# LPC1768.net
KiCad netlist of a schematic drawn in Altium Designer
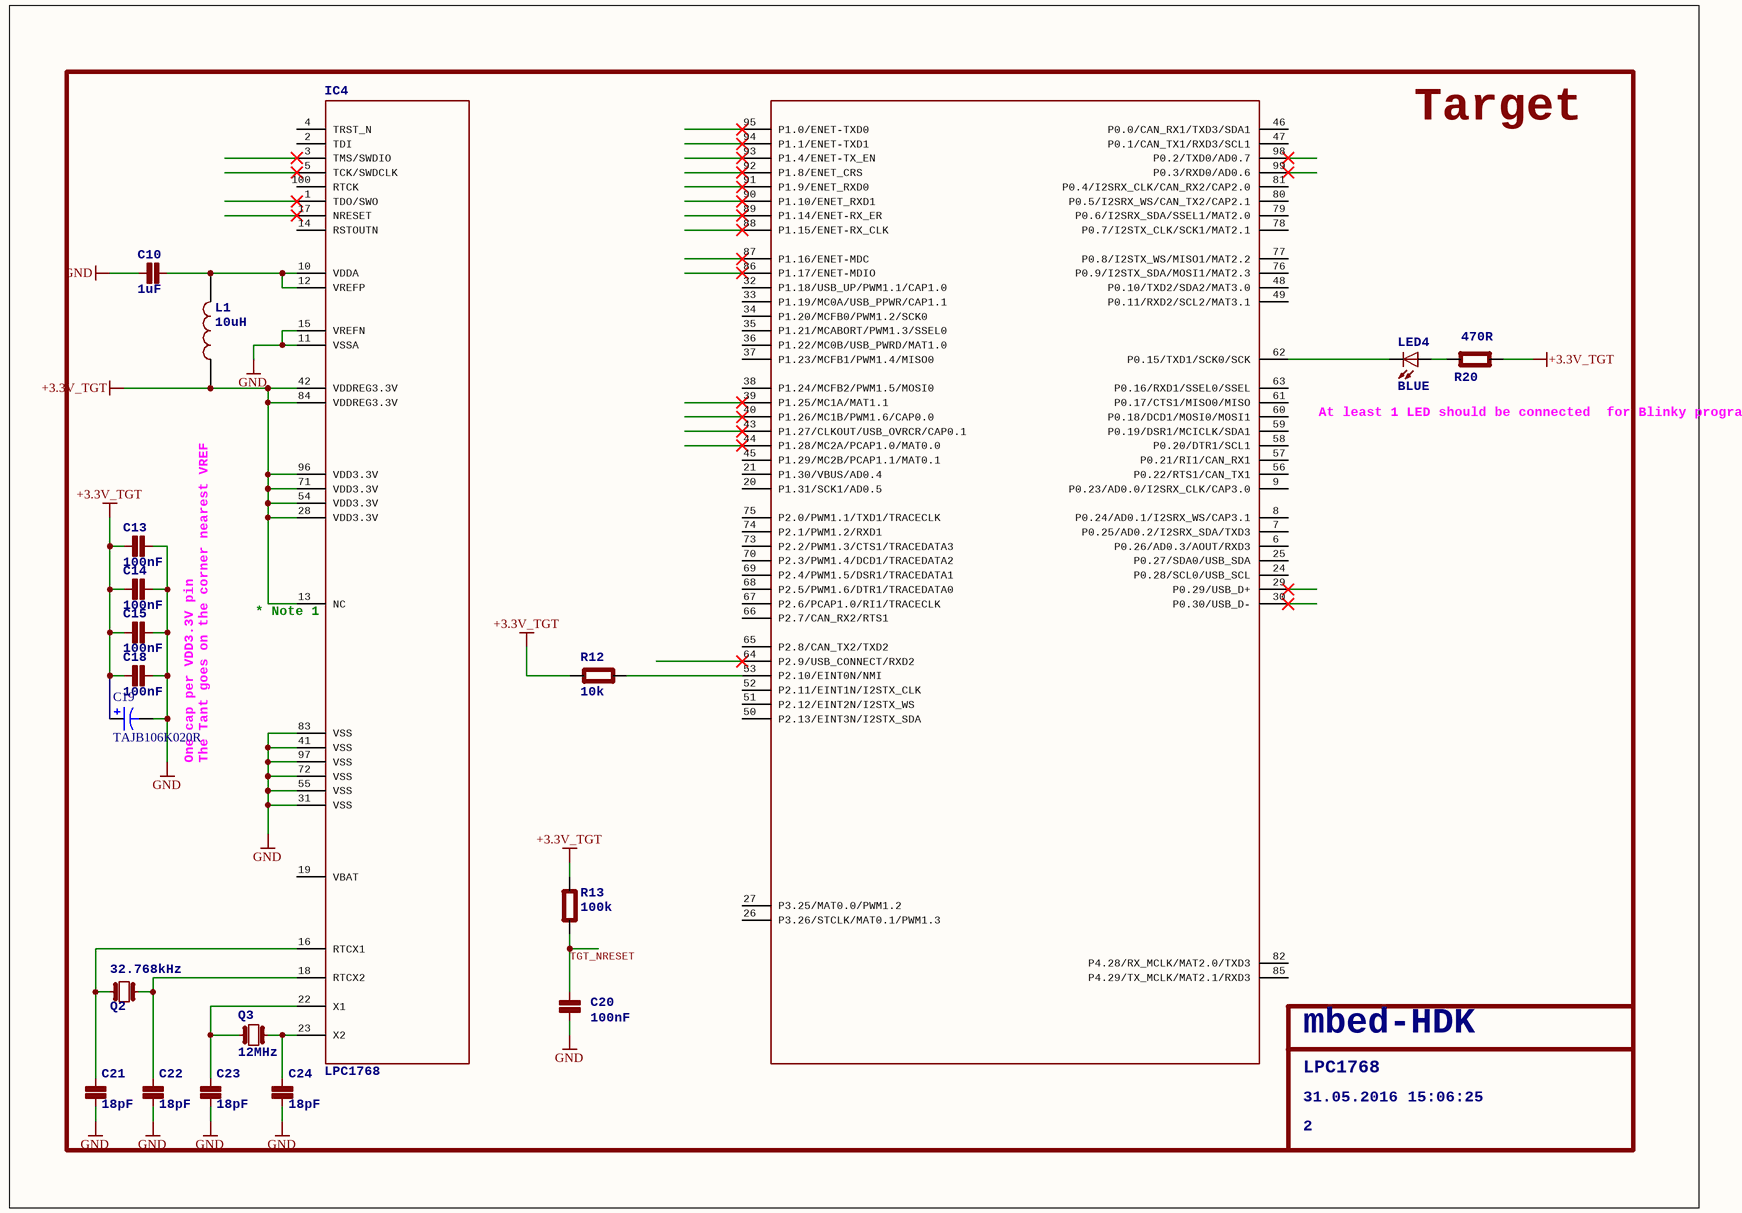
[diagram p0: LPC1768.SchDoc]

(export (version "E")
  (design (tool "Eeschema 10.0.6"))
  (components
    (comp (ref "C10") (value "1uF") (footprint "0603") (libsource (lib "") (part "C0603_2")))
    (comp (ref "C13") (value "100nF") (footprint "0603") (libsource (lib "") (part "C0603_1")))
    (comp (ref "C14") (value "100nF") (footprint "0603") (libsource (lib "") (part "C0603_1")))
    (comp (ref "C15") (value "100nF") (footprint "0603") (libsource (lib "") (part "C0603_1")))
    (comp (ref "C18") (value "100nF") (footprint "0603") (libsource (lib "") (part "C0603_1")))
    (comp (ref "C19")
      (value "TAJB106K020R")
      (footprint "AVX-CAPC3528_V")
      (description "Capacitor, Tantalum, 10uF 10% 20V MCCT-B (3528)")
      (fields (field (name "MANUFACTURER") "AVX") (field (name "TOLERANCE") "10%"))
      (libsource (lib "Altium Content Vault") (part "CMP-0279-00001-1"))
    )
    (comp (ref "C20") (value "100nF") (footprint "0603") (libsource (lib "mbed-HDK") (part "C0603")))
    (comp (ref "C21") (value "18pF") (footprint "0603") (libsource (lib "mbed-HDK") (part "C0603")))
    (comp (ref "C22") (value "18pF") (footprint "0603") (libsource (lib "mbed-HDK") (part "C0603")))
    (comp (ref "C23") (value "18pF") (footprint "0603") (libsource (lib "mbed-HDK") (part "C0603")))
    (comp (ref "C24") (value "18pF") (footprint "0603") (libsource (lib "mbed-HDK") (part "C0603")))
    (comp (ref "IC4") (value "LPC1768") (footprint "LQFP100") (libsource (lib "mbed-HDK") (part "LPC1768")))
    (comp (ref "L1") (value "10uH") (footprint "0603") (libsource (lib "mbed-HDK") (part "L")))
    (comp (ref "LED4")
      (value "BLUE")
      (footprint "CHIPLED_0603")
      (libsource (lib "mbed-HDK") (part "LED0603"))
    )
    (comp (ref "Q2") (value "32.768kHz") (footprint "FC135") (libsource (lib "mbed-HDK") (part "Q_FC135")))
    (comp (ref "Q3") (value "12MHz") (footprint "HC49UP") (libsource (lib "mbed-HDK") (part "Q_HC49UP")))
    (comp (ref "R12") (value "10k") (footprint "0603") (libsource (lib "mbed-HDK") (part "R0603")))
    (comp (ref "R13") (value "100k") (footprint "0603") (libsource (lib "mbed-HDK") (part "R0603")))
    (comp (ref "R20") (value "470R") (footprint "0603") (libsource (lib "mbed-HDK") (part "R0603")))
  )
  (nets
    (net (code "1") (name "+3.3V_TGT") (class "Default")
      (node (ref "C13") (pin "1") (pinfunction "P$1_1") (pintype "passive"))
      (node (ref "C14") (pin "1") (pinfunction "P$1_1") (pintype "passive"))
      (node (ref "C15") (pin "1") (pinfunction "P$1_1") (pintype "passive"))
      (node (ref "C18") (pin "1") (pinfunction "P$1_1") (pintype "passive"))
      (node (ref "C19") (pin "1") (pinfunction "1_1") (pintype "passive"))
      (node (ref "IC4") (pin "13") (pinfunction "NC_13") (pintype "passive"))
      (node (ref "IC4") (pin "28") (pinfunction "VDD3.3V_28") (pintype "passive"))
      (node (ref "IC4") (pin "42") (pinfunction "VDDREG3.3V_42") (pintype "passive"))
      (node (ref "IC4") (pin "54") (pinfunction "VDD3.3V_54") (pintype "passive"))
      (node (ref "IC4") (pin "71") (pinfunction "VDD3.3V_71") (pintype "passive"))
      (node (ref "IC4") (pin "84") (pinfunction "VDDREG3.3V_84") (pintype "passive"))
      (node (ref "IC4") (pin "96") (pinfunction "VDD3.3V_96") (pintype "passive"))
      (node (ref "L1") (pin "1") (pinfunction "P$1_1") (pintype "passive"))
      (node (ref "R12") (pin "1") (pinfunction "P$1_1") (pintype "passive"))
      (node (ref "R13") (pin "2") (pinfunction "P$2_2") (pintype "passive"))
      (node (ref "R20") (pin "1") (pinfunction "P$1_1") (pintype "passive"))
    )
    (net (code "2") (name "/TGT_NRESET") (class "Default")
      (node (ref "C20") (pin "2") (pinfunction "P$2_2") (pintype "passive"))
      (node (ref "R13") (pin "1") (pinfunction "P$1_1") (pintype "passive"))
    )
    (net (code "3") (name "GND") (class "Default")
      (node (ref "C10") (pin "2") (pinfunction "P$2_2") (pintype "passive"))
      (node (ref "C13") (pin "2") (pinfunction "P$2_2") (pintype "passive"))
      (node (ref "C14") (pin "2") (pinfunction "P$2_2") (pintype "passive"))
      (node (ref "C15") (pin "2") (pinfunction "P$2_2") (pintype "passive"))
      (node (ref "C18") (pin "2") (pinfunction "P$2_2") (pintype "passive"))
      (node (ref "C19") (pin "2") (pinfunction "2_2") (pintype "passive"))
      (node (ref "C20") (pin "1") (pinfunction "P$1_1") (pintype "passive"))
      (node (ref "C21") (pin "1") (pinfunction "P$1_1") (pintype "passive"))
      (node (ref "C22") (pin "1") (pinfunction "P$1_1") (pintype "passive"))
      (node (ref "C23") (pin "1") (pinfunction "P$1_1") (pintype "passive"))
      (node (ref "C24") (pin "1") (pinfunction "P$1_1") (pintype "passive"))
      (node (ref "IC4") (pin "11") (pinfunction "VSSA_11") (pintype "passive"))
      (node (ref "IC4") (pin "15") (pinfunction "VREFN_15") (pintype "passive"))
      (node (ref "IC4") (pin "31") (pinfunction "VSS_31") (pintype "passive"))
      (node (ref "IC4") (pin "41") (pinfunction "VSS_41") (pintype "passive"))
      (node (ref "IC4") (pin "55") (pinfunction "VSS_55") (pintype "passive"))
      (node (ref "IC4") (pin "72") (pinfunction "VSS_72") (pintype "passive"))
      (node (ref "IC4") (pin "83") (pinfunction "VSS_83") (pintype "passive"))
      (node (ref "IC4") (pin "97") (pinfunction "VSS_97") (pintype "passive"))
    )
    (net (code "4") (name "Net-(C10-P$1)") (class "Default")
      (node (ref "C10") (pin "1") (pinfunction "P$1_1") (pintype "passive"))
      (node (ref "IC4") (pin "10") (pinfunction "VDDA_10") (pintype "passive"))
      (node (ref "IC4") (pin "12") (pinfunction "VREFP_12") (pintype "passive"))
      (node (ref "L1") (pin "2") (pinfunction "P$2_2") (pintype "passive"))
    )
    (net (code "5") (name "Net-(C21-P$2)") (class "Default")
      (node (ref "C21") (pin "2") (pinfunction "P$2_2") (pintype "passive"))
      (node (ref "IC4") (pin "16") (pinfunction "RTCX1_16") (pintype "passive"))
      (node (ref "Q2") (pin "X2") (pinfunction "2_X2") (pintype "passive"))
    )
    (net (code "6") (name "Net-(C22-P$2)") (class "Default")
      (node (ref "C22") (pin "2") (pinfunction "P$2_2") (pintype "passive"))
      (node (ref "IC4") (pin "18") (pinfunction "RTCX2_18") (pintype "passive"))
      (node (ref "Q2") (pin "X1") (pinfunction "1_X1") (pintype "passive"))
    )
    (net (code "7") (name "Net-(C23-P$2)") (class "Default")
      (node (ref "C23") (pin "2") (pinfunction "P$2_2") (pintype "passive"))
      (node (ref "IC4") (pin "22") (pinfunction "X1_22") (pintype "passive"))
      (node (ref "Q3") (pin "1") (pinfunction "1_1") (pintype "passive"))
    )
    (net (code "8") (name "Net-(C24-P$2)") (class "Default")
      (node (ref "C24") (pin "2") (pinfunction "P$2_2") (pintype "passive"))
      (node (ref "IC4") (pin "23") (pinfunction "X2_23") (pintype "passive"))
      (node (ref "Q3") (pin "2") (pinfunction "2_2") (pintype "passive"))
    )
    (net (code "9") (name "Net-(IC4-P0.15{slash}TXD1{slash}SCK0{slash}SCK)") (class "Default")
      (node (ref "IC4") (pin "62") (pinfunction "P0.15/TXD1/SCK0/SCK_62") (pintype "passive"))
      (node (ref "LED4") (pin "C") (pinfunction "C_C") (pintype "passive"))
    )
    (net (code "10") (name "Net-(IC4-P2.10{slash}EINT0N{slash}NMI)") (class "Default")
      (node (ref "IC4") (pin "53") (pinfunction "P2.10/EINT0N/NMI_53") (pintype "passive"))
      (node (ref "R12") (pin "2") (pinfunction "P$2_2") (pintype "passive"))
    )
    (net (code "11") (name "Net-(R20-P$2)") (class "Default")
      (node (ref "LED4") (pin "A") (pinfunction "A_A") (pintype "passive"))
      (node (ref "R20") (pin "2") (pinfunction "P$2_2") (pintype "passive"))
    )
    (net (code "12") (name "unconnected-(IC4-NRESET-Pad17)") (class "Default")
      (node (ref "IC4") (pin "17") (pinfunction "NRESET_17") (pintype "passive+no_connect"))
    )
    (net (code "13") (name "unconnected-(IC4-P0.0{slash}CAN_RX1{slash}TXD3{slash}SDA1-Pad46)") (class "Default")
      (node (ref "IC4") (pin "46") (pinfunction "P0.0/CAN_RX1/TXD3/SDA1_46") (pintype "passive"))
    )
    (net (code "14") (name "unconnected-(IC4-P0.1{slash}CAN_TX1{slash}RXD3{slash}SCL1-Pad47)") (class "Default")
      (node (ref "IC4") (pin "47") (pinfunction "P0.1/CAN_TX1/RXD3/SCL1_47") (pintype "passive"))
    )
    (net (code "15") (name "unconnected-(IC4-P0.2{slash}TXD0{slash}AD0.7-Pad98)") (class "Default")
      (node (ref "IC4") (pin "98") (pinfunction "P0.2/TXD0/AD0.7_98") (pintype "passive+no_connect"))
    )
    (net (code "16") (name "unconnected-(IC4-P0.3{slash}RXD0{slash}AD0.6-Pad99)") (class "Default")
      (node (ref "IC4") (pin "99") (pinfunction "P0.3/RXD0/AD0.6_99") (pintype "passive+no_connect"))
    )
    (net (code "17") (name "unconnected-(IC4-P0.4{slash}I2SRX_CLK{slash}CAN_RX2{slash}CAP2.0-Pad81)") (class "Default")
      (node (ref "IC4") (pin "81") (pinfunction "P0.4/I2SRX_CLK/CAN_RX2/CAP2.0_81") (pintype "passive"))
    )
    (net (code "18") (name "unconnected-(IC4-P0.5{slash}I2SRX_WS{slash}CAN_TX2{slash}CAP2.1-Pad80)") (class "Default")
      (node (ref "IC4") (pin "80") (pinfunction "P0.5/I2SRX_WS/CAN_TX2/CAP2.1_80") (pintype "passive"))
    )
    (net (code "19") (name "unconnected-(IC4-P0.6{slash}I2SRX_SDA{slash}SSEL1{slash}MAT2.0-Pad79)") (class "Default")
      (node (ref "IC4") (pin "79") (pinfunction "P0.6/I2SRX_SDA/SSEL1/MAT2.0_79") (pintype "passive"))
    )
    (net (code "20") (name "unconnected-(IC4-P0.7{slash}I2STX_CLK{slash}SCK1{slash}MAT2.1-Pad78)") (class "Default")
      (node (ref "IC4") (pin "78") (pinfunction "P0.7/I2STX_CLK/SCK1/MAT2.1_78") (pintype "passive"))
    )
    (net (code "21") (name "unconnected-(IC4-P0.8{slash}I2STX_WS{slash}MISO1{slash}MAT2.2-Pad77)") (class "Default")
      (node (ref "IC4") (pin "77") (pinfunction "P0.8/I2STX_WS/MISO1/MAT2.2_77") (pintype "passive"))
    )
    (net (code "22") (name "unconnected-(IC4-P0.9{slash}I2STX_SDA{slash}MOSI1{slash}MAT2.3-Pad76)") (class "Default")
      (node (ref "IC4") (pin "76") (pinfunction "P0.9/I2STX_SDA/MOSI1/MAT2.3_76") (pintype "passive"))
    )
    (net (code "23") (name "unconnected-(IC4-P0.10{slash}TXD2{slash}SDA2{slash}MAT3.0-Pad48)") (class "Default")
      (node (ref "IC4") (pin "48") (pinfunction "P0.10/TXD2/SDA2/MAT3.0_48") (pintype "passive"))
    )
    (net (code "24") (name "unconnected-(IC4-P0.11{slash}RXD2{slash}SCL2{slash}MAT3.1-Pad49)") (class "Default")
      (node (ref "IC4") (pin "49") (pinfunction "P0.11/RXD2/SCL2/MAT3.1_49") (pintype "passive"))
    )
    (net (code "25") (name "unconnected-(IC4-P0.16{slash}RXD1{slash}SSEL0{slash}SSEL-Pad63)") (class "Default")
      (node (ref "IC4") (pin "63") (pinfunction "P0.16/RXD1/SSEL0/SSEL_63") (pintype "passive"))
    )
    (net (code "26") (name "unconnected-(IC4-P0.17{slash}CTS1{slash}MISO0{slash}MISO-Pad61)") (class "Default")
      (node (ref "IC4") (pin "61") (pinfunction "P0.17/CTS1/MISO0/MISO_61") (pintype "passive"))
    )
    (net (code "27") (name "unconnected-(IC4-P0.18{slash}DCD1{slash}MOSI0{slash}MOSI1-Pad60)") (class "Default")
      (node (ref "IC4") (pin "60") (pinfunction "P0.18/DCD1/MOSI0/MOSI1_60") (pintype "passive"))
    )
    (net (code "28") (name "unconnected-(IC4-P0.19{slash}DSR1{slash}MCICLK{slash}SDA1-Pad59)") (class "Default")
      (node (ref "IC4") (pin "59") (pinfunction "P0.19/DSR1/MCICLK/SDA1_59") (pintype "passive"))
    )
    (net (code "29") (name "unconnected-(IC4-P0.20{slash}DTR1{slash}SCL1-Pad58)") (class "Default")
      (node (ref "IC4") (pin "58") (pinfunction "P0.20/DTR1/SCL1_58") (pintype "passive"))
    )
    (net (code "30") (name "unconnected-(IC4-P0.21{slash}RI1{slash}CAN_RX1-Pad57)") (class "Default")
      (node (ref "IC4") (pin "57") (pinfunction "P0.21/RI1/CAN_RX1_57") (pintype "passive"))
    )
    (net (code "31") (name "unconnected-(IC4-P0.22{slash}RTS1{slash}CAN_TX1-Pad56)") (class "Default")
      (node (ref "IC4") (pin "56") (pinfunction "P0.22/RTS1/CAN_TX1_56") (pintype "passive"))
    )
    (net (code "32") (name "unconnected-(IC4-P0.23{slash}AD0.0{slash}I2SRX_CLK{slash}CAP3.0-Pad9)") (class "Default")
      (node (ref "IC4") (pin "9") (pinfunction "P0.23/AD0.0/I2SRX_CLK/CAP3.0_9") (pintype "passive"))
    )
    (net (code "33") (name "unconnected-(IC4-P0.24{slash}AD0.1{slash}I2SRX_WS{slash}CAP3.1-Pad8)") (class "Default")
      (node (ref "IC4") (pin "8") (pinfunction "P0.24/AD0.1/I2SRX_WS/CAP3.1_8") (pintype "passive"))
    )
    (net (code "34") (name "unconnected-(IC4-P0.25{slash}AD0.2{slash}I2SRX_SDA{slash}TXD3-Pad7)") (class "Default")
      (node (ref "IC4") (pin "7") (pinfunction "P0.25/AD0.2/I2SRX_SDA/TXD3_7") (pintype "passive"))
    )
    (net (code "35") (name "unconnected-(IC4-P0.26{slash}AD0.3{slash}AOUT{slash}RXD3-Pad6)") (class "Default")
      (node (ref "IC4") (pin "6") (pinfunction "P0.26/AD0.3/AOUT/RXD3_6") (pintype "passive"))
    )
    (net (code "36") (name "unconnected-(IC4-P0.27{slash}SDA0{slash}USB_SDA-Pad25)") (class "Default")
      (node (ref "IC4") (pin "25") (pinfunction "P0.27/SDA0/USB_SDA_25") (pintype "passive"))
    )
    (net (code "37") (name "unconnected-(IC4-P0.28{slash}SCL0{slash}USB_SCL-Pad24)") (class "Default")
      (node (ref "IC4") (pin "24") (pinfunction "P0.28/SCL0/USB_SCL_24") (pintype "passive"))
    )
    (net (code "38") (name "unconnected-(IC4-P0.29{slash}USB_D+-Pad29)") (class "Default")
      (node (ref "IC4") (pin "29") (pinfunction "P0.29/USB_D+_29") (pintype "passive+no_connect"))
    )
    (net (code "39") (name "unconnected-(IC4-P0.30{slash}USB_D--Pad30)") (class "Default")
      (node (ref "IC4") (pin "30") (pinfunction "P0.30/USB_D-_30") (pintype "passive+no_connect"))
    )
    (net (code "40") (name "unconnected-(IC4-P1.0{slash}ENET-TXD0-Pad95)") (class "Default")
      (node (ref "IC4") (pin "95") (pinfunction "P1.0/ENET-TXD0_95") (pintype "passive+no_connect"))
    )
    (net (code "41") (name "unconnected-(IC4-P1.1{slash}ENET-TXD1-Pad94)") (class "Default")
      (node (ref "IC4") (pin "94") (pinfunction "P1.1/ENET-TXD1_94") (pintype "passive+no_connect"))
    )
    (net (code "42") (name "unconnected-(IC4-P1.4{slash}ENET-TX_EN-Pad93)") (class "Default")
      (node (ref "IC4") (pin "93") (pinfunction "P1.4/ENET-TX_EN_93") (pintype "passive+no_connect"))
    )
    (net (code "43") (name "unconnected-(IC4-P1.8{slash}ENET_CRS-Pad92)") (class "Default")
      (node (ref "IC4") (pin "92") (pinfunction "P1.8/ENET_CRS_92") (pintype "passive+no_connect"))
    )
    (net (code "44") (name "unconnected-(IC4-P1.9{slash}ENET_RXD0-Pad91)") (class "Default")
      (node (ref "IC4") (pin "91") (pinfunction "P1.9/ENET_RXD0_91") (pintype "passive+no_connect"))
    )
    (net (code "45") (name "unconnected-(IC4-P1.10{slash}ENET_RXD1-Pad90)") (class "Default")
      (node (ref "IC4") (pin "90") (pinfunction "P1.10/ENET_RXD1_90") (pintype "passive+no_connect"))
    )
    (net (code "46") (name "unconnected-(IC4-P1.14{slash}ENET-RX_ER-Pad89)") (class "Default")
      (node (ref "IC4") (pin "89") (pinfunction "P1.14/ENET-RX_ER_89") (pintype "passive+no_connect"))
    )
    (net (code "47") (name "unconnected-(IC4-P1.15{slash}ENET-RX_CLK-Pad88)") (class "Default")
      (node (ref "IC4") (pin "88") (pinfunction "P1.15/ENET-RX_CLK_88") (pintype "passive+no_connect"))
    )
    (net (code "48") (name "unconnected-(IC4-P1.16{slash}ENET-MDC-Pad87)") (class "Default")
      (node (ref "IC4") (pin "87") (pinfunction "P1.16/ENET-MDC_87") (pintype "passive+no_connect"))
    )
    (net (code "49") (name "unconnected-(IC4-P1.17{slash}ENET-MDIO-Pad86)") (class "Default")
      (node (ref "IC4") (pin "86") (pinfunction "P1.17/ENET-MDIO_86") (pintype "passive+no_connect"))
    )
    (net (code "50") (name "unconnected-(IC4-P1.18{slash}USB_UP{slash}PWM1.1{slash}CAP1.0-Pad32)") (class "Default")
      (node (ref "IC4") (pin "32") (pinfunction "P1.18/USB_UP/PWM1.1/CAP1.0_32") (pintype "passive"))
    )
    (net (code "51") (name "unconnected-(IC4-P1.19{slash}MC0A{slash}USB_PPWR{slash}CAP1.1-Pad33)") (class "Default")
      (node (ref "IC4") (pin "33") (pinfunction "P1.19/MC0A/USB_PPWR/CAP1.1_33") (pintype "passive"))
    )
    (net (code "52") (name "unconnected-(IC4-P1.20{slash}MCFB0{slash}PWM1.2{slash}SCK0-Pad34)") (class "Default")
      (node (ref "IC4") (pin "34") (pinfunction "P1.20/MCFB0/PWM1.2/SCK0_34") (pintype "passive"))
    )
    (net (code "53") (name "unconnected-(IC4-P1.21{slash}MCABORT{slash}PWM1.3{slash}SSEL0-Pad35)") (class "Default")
      (node (ref "IC4") (pin "35") (pinfunction "P1.21/MCABORT/PWM1.3/SSEL0_35") (pintype "passive"))
    )
    (net (code "54") (name "unconnected-(IC4-P1.22{slash}MC0B{slash}USB_PWRD{slash}MAT1.0-Pad36)") (class "Default")
      (node (ref "IC4") (pin "36") (pinfunction "P1.22/MC0B/USB_PWRD/MAT1.0_36") (pintype "passive"))
    )
    (net (code "55") (name "unconnected-(IC4-P1.23{slash}MCFB1{slash}PWM1.4{slash}MISO0-Pad37)") (class "Default")
      (node (ref "IC4") (pin "37") (pinfunction "P1.23/MCFB1/PWM1.4/MISO0_37") (pintype "passive"))
    )
    (net (code "56") (name "unconnected-(IC4-P1.24{slash}MCFB2{slash}PWM1.5{slash}MOSI0-Pad38)") (class "Default")
      (node (ref "IC4") (pin "38") (pinfunction "P1.24/MCFB2/PWM1.5/MOSI0_38") (pintype "passive"))
    )
    (net (code "57") (name "unconnected-(IC4-P1.25{slash}MC1A{slash}MAT1.1-Pad39)") (class "Default")
      (node (ref "IC4") (pin "39") (pinfunction "P1.25/MC1A/MAT1.1_39") (pintype "passive+no_connect"))
    )
    (net (code "58") (name "unconnected-(IC4-P1.26{slash}MC1B{slash}PWM1.6{slash}CAP0.0-Pad40)") (class "Default")
      (node (ref "IC4") (pin "40") (pinfunction "P1.26/MC1B/PWM1.6/CAP0.0_40") (pintype "passive+no_connect"))
    )
    (net (code "59") (name "unconnected-(IC4-P1.27{slash}CLKOUT{slash}USB_OVRCR{slash}CAP0.1-Pad43)") (class "Default")
      (node (ref "IC4") (pin "43") (pinfunction "P1.27/CLKOUT/USB_OVRCR/CAP0.1_43") (pintype "passive+no_connect"))
    )
    (net (code "60") (name "unconnected-(IC4-P1.28{slash}MC2A{slash}PCAP1.0{slash}MAT0.0-Pad44)") (class "Default")
      (node (ref "IC4") (pin "44") (pinfunction "P1.28/MC2A/PCAP1.0/MAT0.0_44") (pintype "passive+no_connect"))
    )
    (net (code "61") (name "unconnected-(IC4-P1.29{slash}MC2B{slash}PCAP1.1{slash}MAT0.1-Pad45)") (class "Default")
      (node (ref "IC4") (pin "45") (pinfunction "P1.29/MC2B/PCAP1.1/MAT0.1_45") (pintype "passive"))
    )
    (net (code "62") (name "unconnected-(IC4-P1.30{slash}VBUS{slash}AD0.4-Pad21)") (class "Default")
      (node (ref "IC4") (pin "21") (pinfunction "P1.30/VBUS/AD0.4_21") (pintype "passive"))
    )
    (net (code "63") (name "unconnected-(IC4-P1.31{slash}SCK1{slash}AD0.5-Pad20)") (class "Default")
      (node (ref "IC4") (pin "20") (pinfunction "P1.31/SCK1/AD0.5_20") (pintype "passive"))
    )
    (net (code "64") (name "unconnected-(IC4-P2.0{slash}PWM1.1{slash}TXD1{slash}TRACECLK-Pad75)") (class "Default")
      (node (ref "IC4") (pin "75") (pinfunction "P2.0/PWM1.1/TXD1/TRACECLK_75") (pintype "passive"))
    )
    (net (code "65") (name "unconnected-(IC4-P2.1{slash}PWM1.2{slash}RXD1-Pad74)") (class "Default")
      (node (ref "IC4") (pin "74") (pinfunction "P2.1/PWM1.2/RXD1_74") (pintype "passive"))
    )
    (net (code "66") (name "unconnected-(IC4-P2.2{slash}PWM1.3{slash}CTS1{slash}TRACEDATA3-Pad73)") (class "Default")
      (node (ref "IC4") (pin "73") (pinfunction "P2.2/PWM1.3/CTS1/TRACEDATA3_73") (pintype "passive"))
    )
    (net (code "67") (name "unconnected-(IC4-P2.3{slash}PWM1.4{slash}DCD1{slash}TRACEDATA2-Pad70)") (class "Default")
      (node (ref "IC4") (pin "70") (pinfunction "P2.3/PWM1.4/DCD1/TRACEDATA2_70") (pintype "passive"))
    )
    (net (code "68") (name "unconnected-(IC4-P2.4{slash}PWM1.5{slash}DSR1{slash}TRACEDATA1-Pad69)") (class "Default")
      (node (ref "IC4") (pin "69") (pinfunction "P2.4/PWM1.5/DSR1/TRACEDATA1_69") (pintype "passive"))
    )
    (net (code "69") (name "unconnected-(IC4-P2.5{slash}PWM1.6{slash}DTR1{slash}TRACEDATA0-Pad68)") (class "Default")
      (node (ref "IC4") (pin "68") (pinfunction "P2.5/PWM1.6/DTR1/TRACEDATA0_68") (pintype "passive"))
    )
    (net (code "70") (name "unconnected-(IC4-P2.6{slash}PCAP1.0{slash}RI1{slash}TRACECLK-Pad67)") (class "Default")
      (node (ref "IC4") (pin "67") (pinfunction "P2.6/PCAP1.0/RI1/TRACECLK_67") (pintype "passive"))
    )
    (net (code "71") (name "unconnected-(IC4-P2.7{slash}CAN_RX2{slash}RTS1-Pad66)") (class "Default")
      (node (ref "IC4") (pin "66") (pinfunction "P2.7/CAN_RX2/RTS1_66") (pintype "passive"))
    )
    (net (code "72") (name "unconnected-(IC4-P2.8{slash}CAN_TX2{slash}TXD2-Pad65)") (class "Default")
      (node (ref "IC4") (pin "65") (pinfunction "P2.8/CAN_TX2/TXD2_65") (pintype "passive"))
    )
    (net (code "73") (name "unconnected-(IC4-P2.9{slash}USB_CONNECT{slash}RXD2-Pad64)") (class "Default")
      (node (ref "IC4") (pin "64") (pinfunction "P2.9/USB_CONNECT/RXD2_64") (pintype "passive+no_connect"))
    )
    (net (code "74") (name "unconnected-(IC4-P2.11{slash}EINT1N{slash}I2STX_CLK-Pad52)") (class "Default")
      (node (ref "IC4") (pin "52") (pinfunction "P2.11/EINT1N/I2STX_CLK_52") (pintype "passive"))
    )
    (net (code "75") (name "unconnected-(IC4-P2.12{slash}EINT2N{slash}I2STX_WS-Pad51)") (class "Default")
      (node (ref "IC4") (pin "51") (pinfunction "P2.12/EINT2N/I2STX_WS_51") (pintype "passive"))
    )
    (net (code "76") (name "unconnected-(IC4-P2.13{slash}EINT3N{slash}I2STX_SDA-Pad50)") (class "Default")
      (node (ref "IC4") (pin "50") (pinfunction "P2.13/EINT3N/I2STX_SDA_50") (pintype "passive"))
    )
    (net (code "77") (name "unconnected-(IC4-P3.25{slash}MAT0.0{slash}PWM1.2-Pad27)") (class "Default")
      (node (ref "IC4") (pin "27") (pinfunction "P3.25/MAT0.0/PWM1.2_27") (pintype "passive"))
    )
    (net (code "78") (name "unconnected-(IC4-P3.26{slash}STCLK{slash}MAT0.1{slash}PWM1.3-Pad26)") (class "Default")
      (node (ref "IC4") (pin "26") (pinfunction "P3.26/STCLK/MAT0.1/PWM1.3_26") (pintype "passive"))
    )
    (net (code "79") (name "unconnected-(IC4-P4.28{slash}RX_MCLK{slash}MAT2.0{slash}TXD3-Pad82)") (class "Default")
      (node (ref "IC4") (pin "82") (pinfunction "P4.28/RX_MCLK/MAT2.0/TXD3_82") (pintype "passive"))
    )
    (net (code "80") (name "unconnected-(IC4-P4.29{slash}TX_MCLK{slash}MAT2.1{slash}RXD3-Pad85)") (class "Default")
      (node (ref "IC4") (pin "85") (pinfunction "P4.29/TX_MCLK/MAT2.1/RXD3_85") (pintype "passive"))
    )
    (net (code "81") (name "unconnected-(IC4-RSTOUTN-Pad14)") (class "Default")
      (node (ref "IC4") (pin "14") (pinfunction "RSTOUTN_14") (pintype "passive"))
    )
    (net (code "82") (name "unconnected-(IC4-RTCK-Pad100)") (class "Default")
      (node (ref "IC4") (pin "100") (pinfunction "RTCK_100") (pintype "passive"))
    )
    (net (code "83") (name "unconnected-(IC4-TCK{slash}SWDCLK-Pad5)") (class "Default")
      (node (ref "IC4") (pin "5") (pinfunction "TCK/SWDCLK_5") (pintype "passive+no_connect"))
    )
    (net (code "84") (name "unconnected-(IC4-TDI-Pad2)") (class "Default")
      (node (ref "IC4") (pin "2") (pinfunction "TDI_2") (pintype "passive"))
    )
    (net (code "85") (name "unconnected-(IC4-TDO{slash}SWO-Pad1)") (class "Default")
      (node (ref "IC4") (pin "1") (pinfunction "TDO/SWO_1") (pintype "passive+no_connect"))
    )
    (net (code "86") (name "unconnected-(IC4-TMS{slash}SWDIO-Pad3)") (class "Default")
      (node (ref "IC4") (pin "3") (pinfunction "TMS/SWDIO_3") (pintype "passive+no_connect"))
    )
    (net (code "87") (name "unconnected-(IC4-TRST_N-Pad4)") (class "Default")
      (node (ref "IC4") (pin "4") (pinfunction "TRST_N_4") (pintype "passive"))
    )
    (net (code "88") (name "unconnected-(IC4-VBAT-Pad19)") (class "Default")
      (node (ref "IC4") (pin "19") (pinfunction "VBAT_19") (pintype "passive"))
    )
  )
)
